# seadoo_zs01_pcb.net
KiCad netlist of a schematic drawn in EAGLE
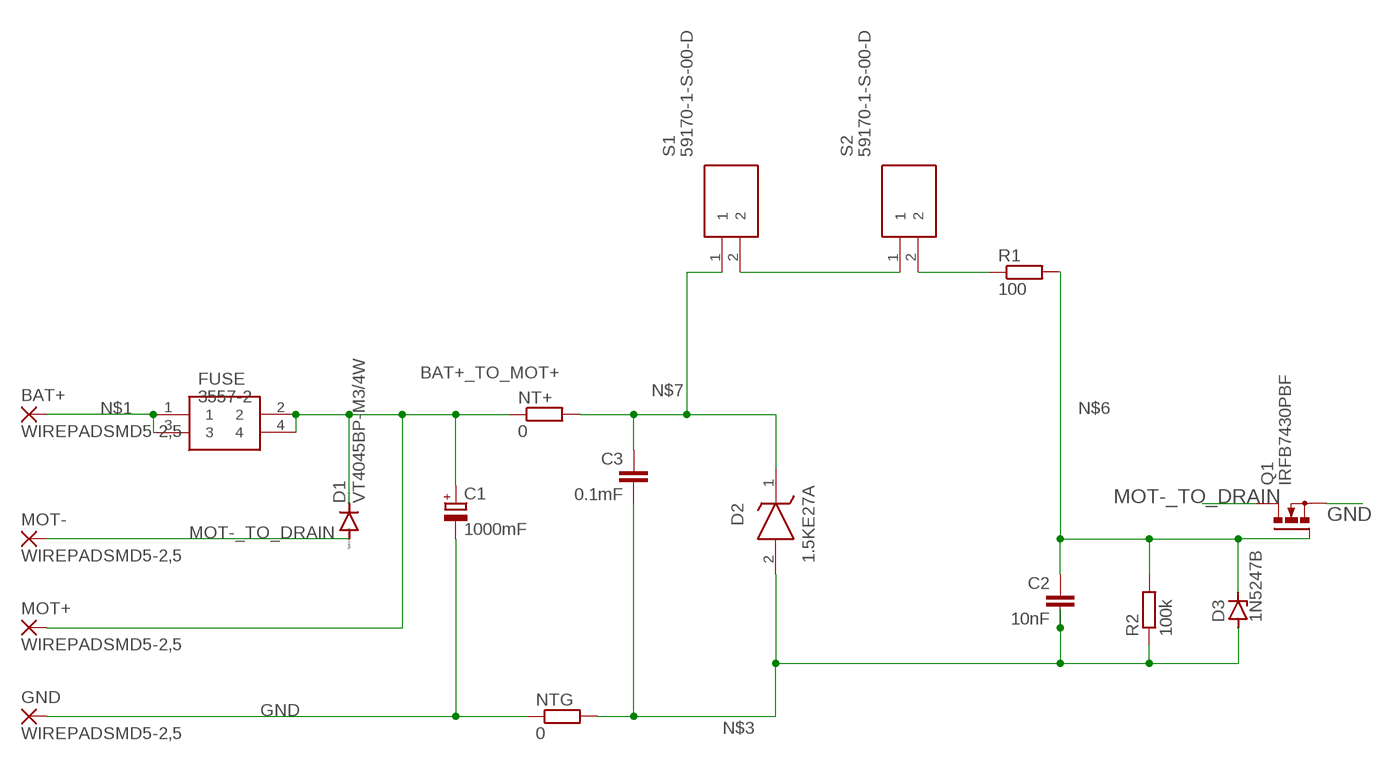
[diagram p0: schematic, sheet 1]

(export (version "E")
  (design (tool "Eeschema 10.0.6"))
  (components
    (comp (ref "BAT+")
      (value "WIREPADSMD5-2,5")
      (footprint "eagle-import:5-2,5")
      (libsource (lib "eagle-import") (part "WIREPADSMD5-2,5"))
    )
    (comp (ref "C1")
      (value "1000mF")
      (footprint "eagle-import:TT5D11")
      (libsource (lib "eagle-import") (part "CPOL-EUTT5D11"))
    )
    (comp (ref "C2")
      (value "10nF")
      (footprint "eagle-import:C5B3")
      (libsource (lib "eagle-import") (part "C5/3"))
    )
    (comp (ref "C3")
      (value "0.1mF")
      (footprint "eagle-import:C5B3")
      (libsource (lib "eagle-import") (part "C5/3"))
    )
    (comp (ref "D1")
      (value "VT4045BP-M3/4W")
      (footprint "eagle-import:TO220AC")
      (libsource (lib "eagle-import") (part "DIODE-TO220H"))
    )
    (comp (ref "D2")
      (value "1.5KE27A")
      (footprint "eagle-import:DIOAD2920W106L900D505")
      (fields (field (name "MOUSER_PART_NUMBER") "511-1.5KE27A"))
      (libsource (lib "eagle-import") (part "1.5KE27A"))
    )
    (comp (ref "D3")
      (value "1N5247B")
      (footprint "eagle-import:P1Z12")
      (libsource (lib "eagle-import") (part "ZENER-DIODEP1-12"))
    )
    (comp (ref "FUSE")
      (value "3557-2")
      (footprint "eagle-import:3557-2")
      (libsource (lib "eagle-import") (part "3557-2"))
    )
    (comp (ref "GND")
      (value "WIREPADSMD5-2,5")
      (footprint "eagle-import:5-2,5")
      (libsource (lib "eagle-import") (part "WIREPADSMD5-2,5"))
    )
    (comp (ref "MOT+")
      (value "WIREPADSMD5-2,5")
      (footprint "eagle-import:5-2,5")
      (libsource (lib "eagle-import") (part "WIREPADSMD5-2,5"))
    )
    (comp (ref "MOT-")
      (value "WIREPADSMD5-2,5")
      (footprint "eagle-import:5-2,5")
      (libsource (lib "eagle-import") (part "WIREPADSMD5-2,5"))
    )
    (comp (ref "NT+")
      (value "0")
      (footprint "eagle-import:R1218")
      (libsource (lib "eagle-import") (part "R-EU_R1218"))
    )
    (comp (ref "NTG")
      (value "0")
      (footprint "eagle-import:R1218")
      (libsource (lib "eagle-import") (part "R-EU_R1218"))
    )
    (comp (ref "Q1")
      (value "IRFB7430PBF")
      (footprint "eagle-import:TO220BH")
      (libsource (lib "eagle-import") (part "PMOSFET_NTO220BH"))
    )
    (comp (ref "R1")
      (value "100")
      (footprint "eagle-import:0204_7")
      (libsource (lib "eagle-import") (part "R-EU_0204/7"))
    )
    (comp (ref "R2")
      (value "100k")
      (footprint "eagle-import:0204_7")
      (libsource (lib "eagle-import") (part "R-EU_0204/7"))
    )
    (comp (ref "S1")
      (value "59170-1-S-00-D")
      (footprint "eagle-import:591701S00D")
      (libsource (lib "eagle-import") (part "59170-1-S-00-D"))
    )
    (comp (ref "S2")
      (value "59170-1-S-00-D")
      (footprint "eagle-import:591701S00D")
      (libsource (lib "eagle-import") (part "59170-1-S-00-D"))
    )
  )
  (nets
    (net (code "1") (name "/BAT+_TO_MOT+") (class "Default")
      (node (ref "C1") (pin "+") (pinfunction "+_+") (pintype "passive"))
      (node (ref "D1") (pin "C") (pinfunction "C_C") (pintype "passive"))
      (node (ref "FUSE") (pin "2") (pinfunction "2_2") (pintype "bidirectional"))
      (node (ref "FUSE") (pin "4") (pinfunction "4_4") (pintype "bidirectional"))
      (node (ref "MOT+") (pin "1") (pinfunction "P_1") (pintype "passive"))
      (node (ref "NT+") (pin "1") (pinfunction "1_1") (pintype "passive"))
    )
    (net (code "2") (name "/GND") (class "Default")
      (node (ref "C1") (pin "-") (pinfunction "-_-") (pintype "passive"))
      (node (ref "GND") (pin "1") (pinfunction "P_1") (pintype "passive"))
      (node (ref "NTG") (pin "1") (pinfunction "1_1") (pintype "passive"))
      (node (ref "Q1") (pin "S") (pinfunction "S_S") (pintype "passive"))
    )
    (net (code "3") (name "/MOT-_TO_DRAIN") (class "Default")
      (node (ref "D1") (pin "A") (pinfunction "A_A") (pintype "passive"))
      (node (ref "MOT-") (pin "1") (pinfunction "P_1") (pintype "passive"))
      (node (ref "Q1") (pin "D") (pinfunction "D_D") (pintype "passive"))
    )
    (net (code "4") (name "/N$1") (class "Default")
      (node (ref "BAT+") (pin "1") (pinfunction "P_1") (pintype "passive"))
      (node (ref "FUSE") (pin "1") (pinfunction "1_1") (pintype "bidirectional"))
      (node (ref "FUSE") (pin "3") (pinfunction "3_3") (pintype "bidirectional"))
    )
    (net (code "5") (name "/N$3") (class "Default")
      (node (ref "C2") (pin "2") (pinfunction "2_2") (pintype "passive"))
      (node (ref "C3") (pin "2") (pinfunction "2_2") (pintype "passive"))
      (node (ref "D2") (pin "2") (pinfunction "A_2") (pintype "bidirectional"))
      (node (ref "D3") (pin "A") (pinfunction "A_A") (pintype "passive"))
      (node (ref "NTG") (pin "2") (pinfunction "2_2") (pintype "passive"))
      (node (ref "R2") (pin "1") (pinfunction "1_1") (pintype "passive"))
    )
    (net (code "6") (name "/N$6") (class "Default")
      (node (ref "C2") (pin "1") (pinfunction "1_1") (pintype "passive"))
      (node (ref "D3") (pin "C") (pinfunction "C_C") (pintype "passive"))
      (node (ref "Q1") (pin "G") (pinfunction "G_G") (pintype "passive"))
      (node (ref "R1") (pin "2") (pinfunction "2_2") (pintype "passive"))
      (node (ref "R2") (pin "2") (pinfunction "2_2") (pintype "passive"))
    )
    (net (code "7") (name "/N$7") (class "Default")
      (node (ref "C3") (pin "1") (pinfunction "1_1") (pintype "passive"))
      (node (ref "D2") (pin "1") (pinfunction "K_1") (pintype "bidirectional"))
      (node (ref "NT+") (pin "2") (pinfunction "2_2") (pintype "passive"))
      (node (ref "S1") (pin "1") (pinfunction "1_1") (pintype "bidirectional"))
    )
    (net (code "8") (name "Net-(R1-Pad1)") (class "Default")
      (node (ref "R1") (pin "1") (pinfunction "1_1") (pintype "passive"))
      (node (ref "S2") (pin "2") (pinfunction "2_2") (pintype "bidirectional"))
    )
    (net (code "9") (name "Net-(S1-Pad2)") (class "Default")
      (node (ref "S1") (pin "2") (pinfunction "2_2") (pintype "bidirectional"))
      (node (ref "S2") (pin "1") (pinfunction "1_1") (pintype "bidirectional"))
    )
  )
)
